# Home_control_v0.net
KiCad netlist of a schematic drawn in EAGLE
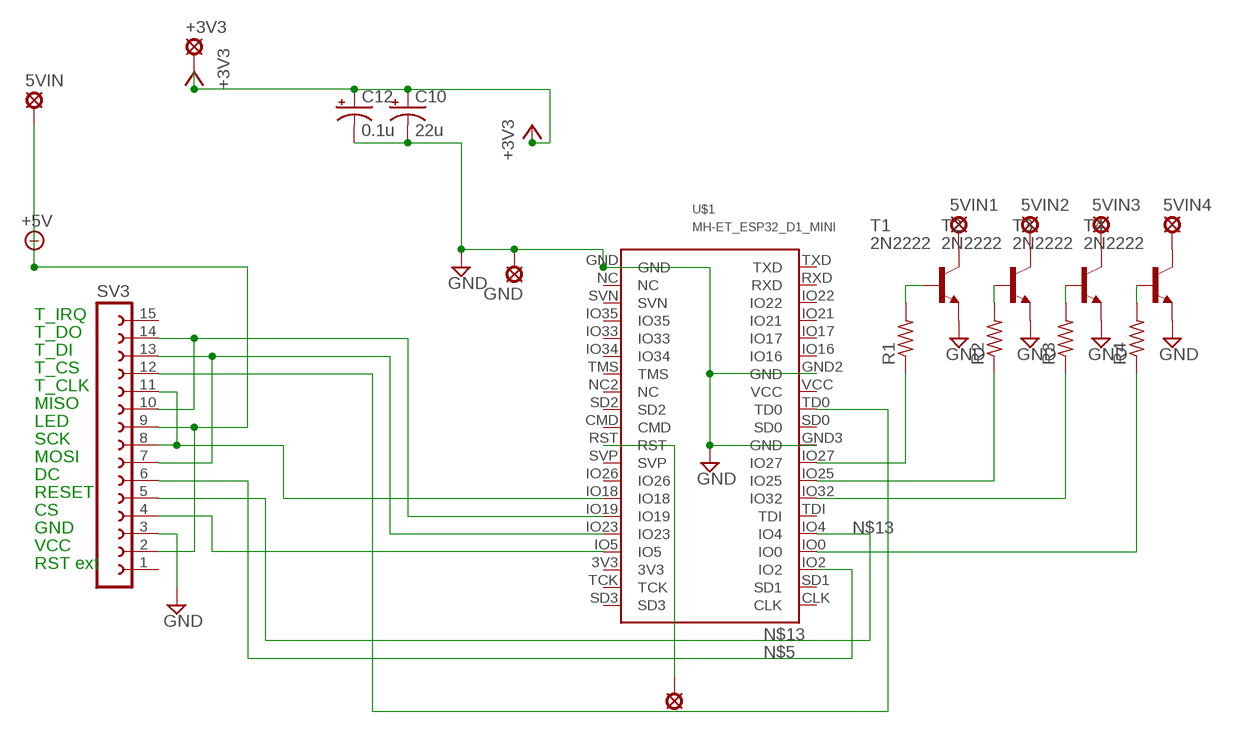
[diagram p0: schematic, sheet 1]

(export (version "E")
  (design (tool "Eeschema 10.0.6"))
  (components
    (comp (ref "+3V3")
      (value "LSP10")
      (footprint "eagle-import:LSP10")
      (libsource (lib "eagle-import") (part "LSP10"))
    )
    (comp (ref "5VIN")
      (value "LSP10")
      (footprint "eagle-import:LSP10")
      (libsource (lib "eagle-import") (part "LSP10"))
    )
    (comp (ref "5VIN1")
      (value "LSP10")
      (footprint "eagle-import:LSP10")
      (libsource (lib "eagle-import") (part "LSP10"))
    )
    (comp (ref "5VIN2")
      (value "LSP10")
      (footprint "eagle-import:LSP10")
      (libsource (lib "eagle-import") (part "LSP10"))
    )
    (comp (ref "5VIN3")
      (value "LSP10")
      (footprint "eagle-import:LSP10")
      (libsource (lib "eagle-import") (part "LSP10"))
    )
    (comp (ref "5VIN4")
      (value "LSP10")
      (footprint "eagle-import:LSP10")
      (libsource (lib "eagle-import") (part "LSP10"))
    )
    (comp (ref "C10")
      (value "22u")
      (footprint "eagle-import:E3,5-8")
      (libsource (lib "eagle-import") (part "CPOL-USE3.5-8"))
    )
    (comp (ref "C12")
      (value "0.1u")
      (footprint "eagle-import:E2-5")
      (libsource (lib "eagle-import") (part "CPOL-USE2-5"))
    )
    (comp (ref "GND")
      (value "LSP10")
      (footprint "eagle-import:LSP10")
      (libsource (lib "eagle-import") (part "LSP10"))
    )
    (comp (ref "R1")
      (value "R-US_R0603")
      (footprint "eagle-import:R0603")
      (libsource (lib "eagle-import") (part "R-US_R0603"))
    )
    (comp (ref "R2")
      (value "R-US_R0603")
      (footprint "eagle-import:R0603")
      (libsource (lib "eagle-import") (part "R-US_R0603"))
    )
    (comp (ref "R3")
      (value "R-US_R0603")
      (footprint "eagle-import:R0603")
      (libsource (lib "eagle-import") (part "R-US_R0603"))
    )
    (comp (ref "R4")
      (value "R-US_R0603")
      (footprint "eagle-import:R0603")
      (libsource (lib "eagle-import") (part "R-US_R0603"))
    )
    (comp (ref "RST")
      (value "LSP10")
      (footprint "eagle-import:LSP10")
      (libsource (lib "eagle-import") (part "LSP10"))
    )
    (comp (ref "SV3")
      (value "FE15-1")
      (footprint "eagle-import:FE15")
      (libsource (lib "eagle-import") (part "FE15-1"))
    )
    (comp (ref "T1")
      (value "2N2222")
      (footprint "eagle-import:TO92-EBC-OVAL")
      (libsource (lib "eagle-import") (part "2N2222"))
    )
    (comp (ref "T2")
      (value "2N2222")
      (footprint "eagle-import:TO92-EBC-OVAL")
      (libsource (lib "eagle-import") (part "2N2222"))
    )
    (comp (ref "T3")
      (value "2N2222")
      (footprint "eagle-import:TO92-EBC-OVAL")
      (libsource (lib "eagle-import") (part "2N2222"))
    )
    (comp (ref "T4")
      (value "2N2222")
      (footprint "eagle-import:TO92-EBC-OVAL")
      (libsource (lib "eagle-import") (part "2N2222"))
    )
    (comp (ref "U$1")
      (value "MH-ET_ESP32_D1_MINI")
      (footprint "eagle-import:MH-ET_ESP32_D1_MINI")
      (libsource (lib "eagle-import") (part "MH-ET_ESP32_D1_MINI"))
    )
  )
  (nets
    (net (code "1") (name "+3V3") (class "Default")
      (node (ref "+3V3") (pin "MP") (pinfunction "MP_MP") (pintype "passive"))
      (node (ref "C10") (pin "+") (pinfunction "+_+") (pintype "passive"))
      (node (ref "C12") (pin "+") (pinfunction "+_+") (pintype "passive"))
    )
    (net (code "2") (name "+5V") (class "Default")
      (node (ref "5VIN") (pin "MP") (pinfunction "MP_MP") (pintype "passive"))
      (node (ref "SV3") (pin "2") (pinfunction "2_2") (pintype "passive"))
      (node (ref "SV3") (pin "9") (pinfunction "9_9") (pintype "passive"))
    )
    (net (code "3") (name "/N$5") (class "Default")
      (node (ref "SV3") (pin "6") (pinfunction "6_6") (pintype "passive"))
      (node (ref "U$1") (pin "IO2") (pinfunction "IO2_IO2") (pintype "bidirectional"))
    )
    (net (code "4") (name "/N$13") (class "Default")
      (node (ref "SV3") (pin "5") (pinfunction "5_5") (pintype "passive"))
      (node (ref "U$1") (pin "IO4") (pinfunction "IO4_IO4") (pintype "bidirectional"))
    )
    (net (code "5") (name "GND") (class "Default")
      (node (ref "C10") (pin "-") (pinfunction "-_-") (pintype "passive"))
      (node (ref "C12") (pin "-") (pinfunction "-_-") (pintype "passive"))
      (node (ref "GND") (pin "MP") (pinfunction "MP_MP") (pintype "passive"))
      (node (ref "SV3") (pin "3") (pinfunction "3_3") (pintype "passive"))
      (node (ref "T1") (pin "E") (pinfunction "E_E") (pintype "passive"))
      (node (ref "T2") (pin "E") (pinfunction "E_E") (pintype "passive"))
      (node (ref "T3") (pin "E") (pinfunction "E_E") (pintype "passive"))
      (node (ref "T4") (pin "E") (pinfunction "E_E") (pintype "passive"))
      (node (ref "U$1") (pin "GND") (pinfunction "GND_GND") (pintype "bidirectional"))
      (node (ref "U$1") (pin "GND2") (pinfunction "GND_GND2") (pintype "bidirectional"))
      (node (ref "U$1") (pin "GND3") (pinfunction "GND_GND3") (pintype "bidirectional"))
    )
    (net (code "6") (name "Net-(5VIN1-PadMP)") (class "Default")
      (node (ref "5VIN1") (pin "MP") (pinfunction "MP_MP") (pintype "passive"))
      (node (ref "T1") (pin "C") (pinfunction "C_C") (pintype "passive"))
    )
    (net (code "7") (name "Net-(5VIN2-PadMP)") (class "Default")
      (node (ref "5VIN2") (pin "MP") (pinfunction "MP_MP") (pintype "passive"))
      (node (ref "T2") (pin "C") (pinfunction "C_C") (pintype "passive"))
    )
    (net (code "8") (name "Net-(5VIN3-PadMP)") (class "Default")
      (node (ref "5VIN3") (pin "MP") (pinfunction "MP_MP") (pintype "passive"))
      (node (ref "T3") (pin "C") (pinfunction "C_C") (pintype "passive"))
    )
    (net (code "9") (name "Net-(5VIN4-PadMP)") (class "Default")
      (node (ref "5VIN4") (pin "MP") (pinfunction "MP_MP") (pintype "passive"))
      (node (ref "T4") (pin "C") (pinfunction "C_C") (pintype "passive"))
    )
    (net (code "10") (name "Net-(R1-Pad1)") (class "Default")
      (node (ref "R1") (pin "1") (pinfunction "1_1") (pintype "passive"))
      (node (ref "U$1") (pin "IO27") (pinfunction "IO27_IO27") (pintype "bidirectional"))
    )
    (net (code "11") (name "Net-(R1-Pad2)") (class "Default")
      (node (ref "R1") (pin "2") (pinfunction "2_2") (pintype "passive"))
      (node (ref "T1") (pin "B") (pinfunction "B_B") (pintype "passive"))
    )
    (net (code "12") (name "Net-(R2-Pad1)") (class "Default")
      (node (ref "R2") (pin "1") (pinfunction "1_1") (pintype "passive"))
      (node (ref "U$1") (pin "IO25") (pinfunction "IO25_IO25") (pintype "bidirectional"))
    )
    (net (code "13") (name "Net-(R2-Pad2)") (class "Default")
      (node (ref "R2") (pin "2") (pinfunction "2_2") (pintype "passive"))
      (node (ref "T2") (pin "B") (pinfunction "B_B") (pintype "passive"))
    )
    (net (code "14") (name "Net-(R3-Pad1)") (class "Default")
      (node (ref "R3") (pin "1") (pinfunction "1_1") (pintype "passive"))
      (node (ref "U$1") (pin "IO32") (pinfunction "IO32_IO32") (pintype "bidirectional"))
    )
    (net (code "15") (name "Net-(R3-Pad2)") (class "Default")
      (node (ref "R3") (pin "2") (pinfunction "2_2") (pintype "passive"))
      (node (ref "T3") (pin "B") (pinfunction "B_B") (pintype "passive"))
    )
    (net (code "16") (name "Net-(R4-Pad1)") (class "Default")
      (node (ref "R4") (pin "1") (pinfunction "1_1") (pintype "passive"))
      (node (ref "U$1") (pin "IO0") (pinfunction "IO0_IO0") (pintype "bidirectional"))
    )
    (net (code "17") (name "Net-(R4-Pad2)") (class "Default")
      (node (ref "R4") (pin "2") (pinfunction "2_2") (pintype "passive"))
      (node (ref "T4") (pin "B") (pinfunction "B_B") (pintype "passive"))
    )
    (net (code "18") (name "Net-(RST-PadMP)") (class "Default")
      (node (ref "RST") (pin "MP") (pinfunction "MP_MP") (pintype "passive"))
      (node (ref "U$1") (pin "RST") (pinfunction "RST_RST") (pintype "bidirectional"))
    )
    (net (code "19") (name "Net-(SV3-Pad4)") (class "Default")
      (node (ref "SV3") (pin "4") (pinfunction "4_4") (pintype "passive"))
      (node (ref "U$1") (pin "IO5") (pinfunction "IO5_IO5") (pintype "bidirectional"))
    )
    (net (code "20") (name "Net-(SV3-Pad10)") (class "Default")
      (node (ref "SV3") (pin "10") (pinfunction "10_10") (pintype "passive"))
      (node (ref "SV3") (pin "14") (pinfunction "14_14") (pintype "passive"))
      (node (ref "U$1") (pin "IO19") (pinfunction "IO19_IO19") (pintype "bidirectional"))
    )
    (net (code "21") (name "Net-(SV3-Pad11)") (class "Default")
      (node (ref "SV3") (pin "11") (pinfunction "11_11") (pintype "passive"))
      (node (ref "SV3") (pin "8") (pinfunction "8_8") (pintype "passive"))
      (node (ref "U$1") (pin "IO18") (pinfunction "IO18_IO18") (pintype "bidirectional"))
    )
    (net (code "22") (name "Net-(SV3-Pad12)") (class "Default")
      (node (ref "SV3") (pin "12") (pinfunction "12_12") (pintype "passive"))
      (node (ref "U$1") (pin "TD0") (pinfunction "TD0_TD0") (pintype "bidirectional"))
    )
    (net (code "23") (name "Net-(SV3-Pad13)") (class "Default")
      (node (ref "SV3") (pin "13") (pinfunction "13_13") (pintype "passive"))
      (node (ref "SV3") (pin "7") (pinfunction "7_7") (pintype "passive"))
      (node (ref "U$1") (pin "IO23") (pinfunction "IO23_IO23") (pintype "bidirectional"))
    )
    (net (code "24") (name "unconnected-(SV3-Pad1)") (class "Default")
      (node (ref "SV3") (pin "1") (pinfunction "1_1") (pintype "passive"))
    )
    (net (code "25") (name "unconnected-(SV3-Pad15)") (class "Default")
      (node (ref "SV3") (pin "15") (pinfunction "15_15") (pintype "passive"))
    )
    (net (code "26") (name "unconnected-(U$1-NC-PadNC2)") (class "Default")
      (node (ref "U$1") (pin "NC2") (pinfunction "NC_NC2") (pintype "bidirectional"))
    )
    (net (code "27") (name "unconnected-(U$1-Pad3V3)") (class "Default")
      (node (ref "U$1") (pin "3V3") (pinfunction "3V3_3V3") (pintype "bidirectional"))
    )
    (net (code "28") (name "unconnected-(U$1-PadCLK)") (class "Default")
      (node (ref "U$1") (pin "CLK") (pinfunction "CLK_CLK") (pintype "bidirectional"))
    )
    (net (code "29") (name "unconnected-(U$1-PadCMD)") (class "Default")
      (node (ref "U$1") (pin "CMD") (pinfunction "CMD_CMD") (pintype "bidirectional"))
    )
    (net (code "30") (name "unconnected-(U$1-PadIO16)") (class "Default")
      (node (ref "U$1") (pin "IO16") (pinfunction "IO16_IO16") (pintype "bidirectional"))
    )
    (net (code "31") (name "unconnected-(U$1-PadIO17)") (class "Default")
      (node (ref "U$1") (pin "IO17") (pinfunction "IO17_IO17") (pintype "bidirectional"))
    )
    (net (code "32") (name "unconnected-(U$1-PadIO21)") (class "Default")
      (node (ref "U$1") (pin "IO21") (pinfunction "IO21_IO21") (pintype "bidirectional"))
    )
    (net (code "33") (name "unconnected-(U$1-PadIO22)") (class "Default")
      (node (ref "U$1") (pin "IO22") (pinfunction "IO22_IO22") (pintype "bidirectional"))
    )
    (net (code "34") (name "unconnected-(U$1-PadIO26)") (class "Default")
      (node (ref "U$1") (pin "IO26") (pinfunction "IO26_IO26") (pintype "bidirectional"))
    )
    (net (code "35") (name "unconnected-(U$1-PadIO33)") (class "Default")
      (node (ref "U$1") (pin "IO33") (pinfunction "IO33_IO33") (pintype "bidirectional"))
    )
    (net (code "36") (name "unconnected-(U$1-PadIO34)") (class "Default")
      (node (ref "U$1") (pin "IO34") (pinfunction "IO34_IO34") (pintype "bidirectional"))
    )
    (net (code "37") (name "unconnected-(U$1-PadIO35)") (class "Default")
      (node (ref "U$1") (pin "IO35") (pinfunction "IO35_IO35") (pintype "bidirectional"))
    )
    (net (code "38") (name "unconnected-(U$1-PadNC)") (class "Default")
      (node (ref "U$1") (pin "NC") (pinfunction "NC_NC") (pintype "bidirectional"))
    )
    (net (code "39") (name "unconnected-(U$1-PadRXD)") (class "Default")
      (node (ref "U$1") (pin "RXD") (pinfunction "RXD_RXD") (pintype "bidirectional"))
    )
    (net (code "40") (name "unconnected-(U$1-PadSD0)") (class "Default")
      (node (ref "U$1") (pin "SD0") (pinfunction "SD0_SD0") (pintype "bidirectional"))
    )
    (net (code "41") (name "unconnected-(U$1-PadSD1)") (class "Default")
      (node (ref "U$1") (pin "SD1") (pinfunction "SD1_SD1") (pintype "bidirectional"))
    )
    (net (code "42") (name "unconnected-(U$1-PadSD2)") (class "Default")
      (node (ref "U$1") (pin "SD2") (pinfunction "SD2_SD2") (pintype "bidirectional"))
    )
    (net (code "43") (name "unconnected-(U$1-PadSD3)") (class "Default")
      (node (ref "U$1") (pin "SD3") (pinfunction "SD3_SD3") (pintype "bidirectional"))
    )
    (net (code "44") (name "unconnected-(U$1-PadSVN)") (class "Default")
      (node (ref "U$1") (pin "SVN") (pinfunction "SVN_SVN") (pintype "bidirectional"))
    )
    (net (code "45") (name "unconnected-(U$1-PadSVP)") (class "Default")
      (node (ref "U$1") (pin "SVP") (pinfunction "SVP_SVP") (pintype "bidirectional"))
    )
    (net (code "46") (name "unconnected-(U$1-PadTCK)") (class "Default")
      (node (ref "U$1") (pin "TCK") (pinfunction "TCK_TCK") (pintype "bidirectional"))
    )
    (net (code "47") (name "unconnected-(U$1-PadTDI)") (class "Default")
      (node (ref "U$1") (pin "TDI") (pinfunction "TDI_TDI") (pintype "bidirectional"))
    )
    (net (code "48") (name "unconnected-(U$1-PadTMS)") (class "Default")
      (node (ref "U$1") (pin "TMS") (pinfunction "TMS_TMS") (pintype "bidirectional"))
    )
    (net (code "49") (name "unconnected-(U$1-PadTXD)") (class "Default")
      (node (ref "U$1") (pin "TXD") (pinfunction "TXD_TXD") (pintype "bidirectional"))
    )
    (net (code "50") (name "unconnected-(U$1-PadVCC)") (class "Default")
      (node (ref "U$1") (pin "VCC") (pinfunction "VCC_VCC") (pintype "bidirectional"))
    )
  )
)
